# LEDnecklace.net
KiCad netlist of a schematic drawn in EAGLE
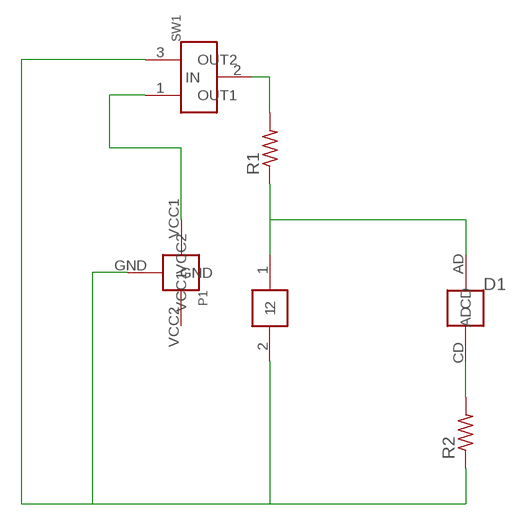
[diagram p0: schematic, sheet 1]

(export (version "E")
  (design (tool "Eeschema 10.0.6"))
  (components
    (comp (ref "D1")
      (value "XLAMP_XBD")
      (footprint "eagle-import:XLAMP_XBD")
      (libsource (lib "eagle-import") (part "XLAMP_XBD"))
    )
    (comp (ref "P1")
      (value "CR1220")
      (footprint "eagle-import:CR1220_1225")
      (libsource (lib "eagle-import") (part "CR1220"))
    )
    (comp (ref "PC1")
      (value "PDV-P8101")
      (footprint "eagle-import:PHOTOCELL_CERAMIC")
      (libsource (lib "eagle-import") (part "PDV-P8101"))
    )
    (comp (ref "R1")
      (value "R-US_R0603")
      (footprint "eagle-import:R0603")
      (libsource (lib "eagle-import") (part "R-US_R0603"))
    )
    (comp (ref "R2")
      (value "R-US_R0603")
      (footprint "eagle-import:R0603")
      (libsource (lib "eagle-import") (part "R-US_R0603"))
    )
    (comp (ref "SW1")
      (value "PCM12SMTR")
      (footprint "eagle-import:PCM12SMTR")
      (libsource (lib "eagle-import") (part "PCM12SMTR"))
    )
  )
  (nets
    (net (code "1") (name "Net-(D1-PadAD)") (class "Default")
      (node (ref "D1") (pin "AD") (pinfunction "AD_AD") (pintype "bidirectional"))
      (node (ref "PC1") (pin "1") (pinfunction "1_1") (pintype "bidirectional"))
      (node (ref "R1") (pin "1") (pinfunction "1_1") (pintype "passive"))
    )
    (net (code "2") (name "Net-(D1-PadCD)") (class "Default")
      (node (ref "D1") (pin "CD") (pinfunction "CD_CD") (pintype "bidirectional"))
      (node (ref "R2") (pin "2") (pinfunction "2_2") (pintype "passive"))
    )
    (net (code "3") (name "Net-(SW1-IN)") (class "Default")
      (node (ref "R1") (pin "2") (pinfunction "2_2") (pintype "passive"))
      (node (ref "SW1") (pin "2") (pinfunction "IN_2") (pintype "bidirectional"))
    )
    (net (code "4") (name "Net-(SW1-OUT1)") (class "Default")
      (node (ref "P1") (pin "VCC1") (pinfunction "VCC1_VCC1") (pintype "bidirectional"))
      (node (ref "SW1") (pin "1") (pinfunction "OUT1_1") (pintype "bidirectional"))
    )
    (net (code "5") (name "Net-(SW1-OUT2)") (class "Default")
      (node (ref "P1") (pin "GND") (pinfunction "GND_GND") (pintype "bidirectional"))
      (node (ref "PC1") (pin "2") (pinfunction "2_2") (pintype "bidirectional"))
      (node (ref "R2") (pin "1") (pinfunction "1_1") (pintype "passive"))
      (node (ref "SW1") (pin "3") (pinfunction "OUT2_3") (pintype "bidirectional"))
    )
    (net (code "6") (name "unconnected-(P1-PadVCC2)") (class "Default")
      (node (ref "P1") (pin "VCC2") (pinfunction "VCC2_VCC2") (pintype "bidirectional"))
    )
  )
)
